# faros-328P-nrf8001-50x50.net
KiCad netlist of a schematic drawn in EAGLE
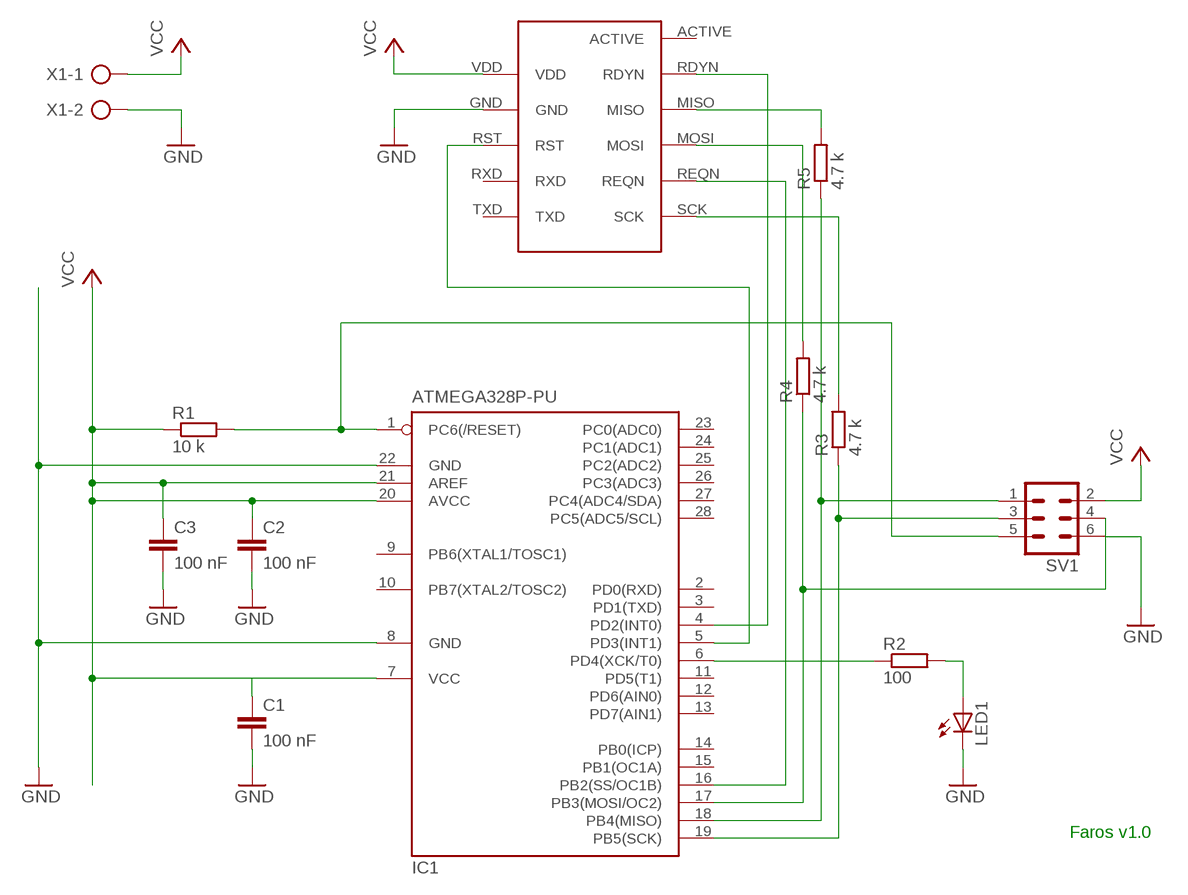
[diagram p0: schematic, sheet 1]

(export (version "E")
  (design (tool "Eeschema 10.0.6"))
  (components
    (comp (ref "C1")
      (value "100 nF")
      (footprint "eagle-import:C050-024X044")
      (libsource (lib "eagle-import") (part "C-EU050-024X044"))
    )
    (comp (ref "C2")
      (value "100 nF")
      (footprint "eagle-import:C050-024X044")
      (libsource (lib "eagle-import") (part "C-EU050-024X044"))
    )
    (comp (ref "C3")
      (value "100 nF")
      (footprint "eagle-import:C050-024X044")
      (libsource (lib "eagle-import") (part "C-EU050-024X044"))
    )
    (comp (ref "IC1")
      (value "ATMEGA328P-PU")
      (footprint "eagle-import:DIL28-3")
      (libsource (lib "eagle-import") (part "MEGA8-P"))
    )
    (comp (ref "LED1")
      (value "LED3MM")
      (footprint "eagle-import:LED3MM")
      (libsource (lib "eagle-import") (part "LED3MM"))
    )
    (comp (ref "MOD1")
      (value "MOD-NRF8001MOD-NRF8001")
      (footprint "eagle-import:MOD-NRF8001")
      (libsource (lib "eagle-import") (part "MOD-NRF8001MOD-NRF8001"))
    )
    (comp (ref "R1")
      (value "10 k")
      (footprint "eagle-import:0207_7")
      (libsource (lib "eagle-import") (part "R-EU_0207/7"))
    )
    (comp (ref "R2")
      (value "100")
      (footprint "eagle-import:0207_7")
      (libsource (lib "eagle-import") (part "R-EU_0207/7"))
    )
    (comp (ref "R3")
      (value "4.7 k")
      (footprint "eagle-import:0207_7")
      (libsource (lib "eagle-import") (part "R-EU_0207/7"))
    )
    (comp (ref "R4")
      (value "4.7 k")
      (footprint "eagle-import:0207_7")
      (libsource (lib "eagle-import") (part "R-EU_0207/7"))
    )
    (comp (ref "R5")
      (value "4.7 k")
      (footprint "eagle-import:0207_7")
      (libsource (lib "eagle-import") (part "R-EU_0207/7"))
    )
    (comp (ref "SV1")
      (value "MA03-2")
      (footprint "eagle-import:MA03-2")
      (libsource (lib "eagle-import") (part "MA03-2"))
    )
    (comp (ref "X1")
      (value "AK500/2")
      (footprint "eagle-import:AK500_2")
      (libsource (lib "eagle-import") (part "AK500/2"))
    )
  )
  (nets
    (net (code "1") (name "GND") (class "Default")
      (node (ref "C1") (pin "2") (pinfunction "2_2") (pintype "passive"))
      (node (ref "C2") (pin "2") (pinfunction "2_2") (pintype "passive"))
      (node (ref "C3") (pin "2") (pinfunction "2_2") (pintype "passive"))
      (node (ref "IC1") (pin "22") (pinfunction "GND_22") (pintype "power_in"))
      (node (ref "IC1") (pin "8") (pinfunction "GND_8") (pintype "power_in"))
      (node (ref "LED1") (pin "K") (pinfunction "C_K") (pintype "passive"))
      (node (ref "MOD1") (pin "GND") (pinfunction "GND_GND") (pintype "power_in"))
      (node (ref "SV1") (pin "6") (pinfunction "6_6") (pintype "passive"))
      (node (ref "X1") (pin "2") (pinfunction "KL_2") (pintype "passive"))
    )
    (net (code "2") (name "Net-(IC1-PB2(SS{slash}OC1B))") (class "Default")
      (node (ref "IC1") (pin "16") (pinfunction "PB2(SS/OC1B)_16") (pintype "bidirectional"))
      (node (ref "MOD1") (pin "REQN") (pinfunction "REQN_REQN") (pintype "input"))
    )
    (net (code "3") (name "Net-(IC1-PB3(MOSI{slash}OC2))") (class "Default")
      (node (ref "IC1") (pin "17") (pinfunction "PB3(MOSI/OC2)_17") (pintype "bidirectional"))
      (node (ref "R4") (pin "1") (pinfunction "1_1") (pintype "passive"))
      (node (ref "SV1") (pin "4") (pinfunction "4_4") (pintype "passive"))
    )
    (net (code "4") (name "Net-(IC1-PB4(MISO))") (class "Default")
      (node (ref "IC1") (pin "18") (pinfunction "PB4(MISO)_18") (pintype "bidirectional"))
      (node (ref "R5") (pin "1") (pinfunction "1_1") (pintype "passive"))
      (node (ref "SV1") (pin "1") (pinfunction "1_1") (pintype "passive"))
    )
    (net (code "5") (name "Net-(IC1-PB5(SCK))") (class "Default")
      (node (ref "IC1") (pin "19") (pinfunction "PB5(SCK)_19") (pintype "bidirectional"))
      (node (ref "R3") (pin "1") (pinfunction "1_1") (pintype "passive"))
      (node (ref "SV1") (pin "3") (pinfunction "3_3") (pintype "passive"))
    )
    (net (code "6") (name "Net-(IC1-PC6({slash}RESET))") (class "Default")
      (node (ref "IC1") (pin "1") (pinfunction "PC6(/RESET)_1") (pintype "bidirectional"))
      (node (ref "R1") (pin "2") (pinfunction "2_2") (pintype "passive"))
      (node (ref "SV1") (pin "5") (pinfunction "5_5") (pintype "passive"))
    )
    (net (code "7") (name "Net-(IC1-PD2(INT0))") (class "Default")
      (node (ref "IC1") (pin "4") (pinfunction "PD2(INT0)_4") (pintype "bidirectional"))
      (node (ref "MOD1") (pin "RDYN") (pinfunction "RDYN_RDYN") (pintype "output"))
    )
    (net (code "8") (name "Net-(IC1-PD3(INT1))") (class "Default")
      (node (ref "IC1") (pin "5") (pinfunction "PD3(INT1)_5") (pintype "bidirectional"))
      (node (ref "MOD1") (pin "RST") (pinfunction "RST_RST") (pintype "input"))
    )
    (net (code "9") (name "Net-(IC1-PD4(XCK{slash}T0))") (class "Default")
      (node (ref "IC1") (pin "6") (pinfunction "PD4(XCK/T0)_6") (pintype "bidirectional"))
      (node (ref "R2") (pin "1") (pinfunction "1_1") (pintype "passive"))
    )
    (net (code "10") (name "Net-(LED1-PadA)") (class "Default")
      (node (ref "LED1") (pin "A") (pinfunction "A_A") (pintype "passive"))
      (node (ref "R2") (pin "2") (pinfunction "2_2") (pintype "passive"))
    )
    (net (code "11") (name "Net-(MOD1-PadMISO)") (class "Default")
      (node (ref "MOD1") (pin "MISO") (pinfunction "MISO_MISO") (pintype "output"))
      (node (ref "R5") (pin "2") (pinfunction "2_2") (pintype "passive"))
    )
    (net (code "12") (name "Net-(MOD1-PadMOSI)") (class "Default")
      (node (ref "MOD1") (pin "MOSI") (pinfunction "MOSI_MOSI") (pintype "input"))
      (node (ref "R4") (pin "2") (pinfunction "2_2") (pintype "passive"))
    )
    (net (code "13") (name "Net-(MOD1-PadSCK)") (class "Default")
      (node (ref "MOD1") (pin "SCK") (pinfunction "SCK_SCK") (pintype "input"))
      (node (ref "R3") (pin "2") (pinfunction "2_2") (pintype "passive"))
    )
    (net (code "14") (name "VCC") (class "Default")
      (node (ref "C1") (pin "1") (pinfunction "1_1") (pintype "passive"))
      (node (ref "C2") (pin "1") (pinfunction "1_1") (pintype "passive"))
      (node (ref "C3") (pin "1") (pinfunction "1_1") (pintype "passive"))
      (node (ref "IC1") (pin "20") (pinfunction "AVCC_20") (pintype "power_in"))
      (node (ref "IC1") (pin "21") (pinfunction "AREF_21") (pintype "passive"))
      (node (ref "IC1") (pin "7") (pinfunction "VCC_7") (pintype "power_in"))
      (node (ref "MOD1") (pin "VDD") (pinfunction "VDD_VDD") (pintype "power_in"))
      (node (ref "R1") (pin "1") (pinfunction "1_1") (pintype "passive"))
      (node (ref "SV1") (pin "2") (pinfunction "2_2") (pintype "passive"))
      (node (ref "X1") (pin "1") (pinfunction "KL_1") (pintype "passive"))
    )
    (net (code "15") (name "unconnected-(IC1-PB0(ICP)-Pad14)") (class "Default")
      (node (ref "IC1") (pin "14") (pinfunction "PB0(ICP)_14") (pintype "bidirectional"))
    )
    (net (code "16") (name "unconnected-(IC1-PB1(OC1A)-Pad15)") (class "Default")
      (node (ref "IC1") (pin "15") (pinfunction "PB1(OC1A)_15") (pintype "bidirectional"))
    )
    (net (code "17") (name "unconnected-(IC1-PB6(XTAL1{slash}TOSC1)-Pad9)") (class "Default")
      (node (ref "IC1") (pin "9") (pinfunction "PB6(XTAL1/TOSC1)_9") (pintype "bidirectional"))
    )
    (net (code "18") (name "unconnected-(IC1-PB7(XTAL2{slash}TOSC2)-Pad10)") (class "Default")
      (node (ref "IC1") (pin "10") (pinfunction "PB7(XTAL2/TOSC2)_10") (pintype "bidirectional"))
    )
    (net (code "19") (name "unconnected-(IC1-PC0(ADC0)-Pad23)") (class "Default")
      (node (ref "IC1") (pin "23") (pinfunction "PC0(ADC0)_23") (pintype "bidirectional"))
    )
    (net (code "20") (name "unconnected-(IC1-PC1(ADC1)-Pad24)") (class "Default")
      (node (ref "IC1") (pin "24") (pinfunction "PC1(ADC1)_24") (pintype "bidirectional"))
    )
    (net (code "21") (name "unconnected-(IC1-PC2(ADC2)-Pad25)") (class "Default")
      (node (ref "IC1") (pin "25") (pinfunction "PC2(ADC2)_25") (pintype "bidirectional"))
    )
    (net (code "22") (name "unconnected-(IC1-PC3(ADC3)-Pad26)") (class "Default")
      (node (ref "IC1") (pin "26") (pinfunction "PC3(ADC3)_26") (pintype "bidirectional"))
    )
    (net (code "23") (name "unconnected-(IC1-PC4(ADC4{slash}SDA)-Pad27)") (class "Default")
      (node (ref "IC1") (pin "27") (pinfunction "PC4(ADC4/SDA)_27") (pintype "bidirectional"))
    )
    (net (code "24") (name "unconnected-(IC1-PC5(ADC5{slash}SCL)-Pad28)") (class "Default")
      (node (ref "IC1") (pin "28") (pinfunction "PC5(ADC5/SCL)_28") (pintype "bidirectional"))
    )
    (net (code "25") (name "unconnected-(IC1-PD0(RXD)-Pad2)") (class "Default")
      (node (ref "IC1") (pin "2") (pinfunction "PD0(RXD)_2") (pintype "bidirectional"))
    )
    (net (code "26") (name "unconnected-(IC1-PD1(TXD)-Pad3)") (class "Default")
      (node (ref "IC1") (pin "3") (pinfunction "PD1(TXD)_3") (pintype "bidirectional"))
    )
    (net (code "27") (name "unconnected-(IC1-PD5(T1)-Pad11)") (class "Default")
      (node (ref "IC1") (pin "11") (pinfunction "PD5(T1)_11") (pintype "bidirectional"))
    )
    (net (code "28") (name "unconnected-(IC1-PD6(AIN0)-Pad12)") (class "Default")
      (node (ref "IC1") (pin "12") (pinfunction "PD6(AIN0)_12") (pintype "bidirectional"))
    )
    (net (code "29") (name "unconnected-(IC1-PD7(AIN1)-Pad13)") (class "Default")
      (node (ref "IC1") (pin "13") (pinfunction "PD7(AIN1)_13") (pintype "bidirectional"))
    )
    (net (code "30") (name "unconnected-(MOD1-PadACTIVE)") (class "Default")
      (node (ref "MOD1") (pin "ACTIVE") (pinfunction "ACTIVE_ACTIVE") (pintype "output"))
    )
    (net (code "31") (name "unconnected-(MOD1-PadRXD)") (class "Default")
      (node (ref "MOD1") (pin "RXD") (pinfunction "RXD_RXD") (pintype "input"))
    )
    (net (code "32") (name "unconnected-(MOD1-PadTXD)") (class "Default")
      (node (ref "MOD1") (pin "TXD") (pinfunction "TXD_TXD") (pintype "output"))
    )
  )
)
